# v1.net
KiCad netlist of a schematic drawn in EAGLE
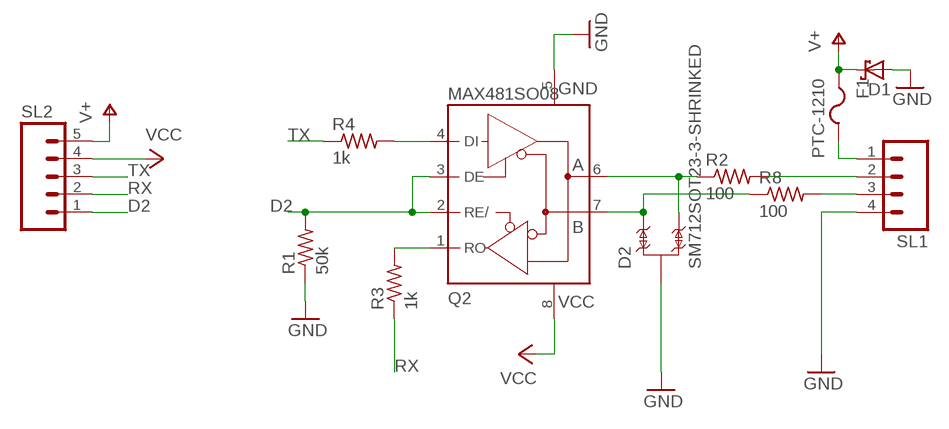
[diagram p0: schematic, sheet 1]

(export (version "E")
  (design (tool "Eeschema 10.0.6"))
  (components
    (comp (ref "D1")
      (value "SCHOTTKY-DIODESMC")
      (footprint "eagle-import:SMC")
      (libsource (lib "eagle-import") (part "SCHOTTKY-DIODESMC"))
    )
    (comp (ref "D2")
      (value "SM712SOT23-3-SHRINKED")
      (footprint "eagle-import:SOT23-3-SHRINKED")
      (libsource (lib "eagle-import") (part "SM712SOT23-3-SHRINKED"))
    )
    (comp (ref "F1")
      (value "PTC-1210")
      (footprint "eagle-import:1210")
      (libsource (lib "eagle-import") (part "PTC-1210"))
    )
    (comp (ref "Q2")
      (value "MAX481SO08")
      (footprint "eagle-import:SO08")
      (libsource (lib "eagle-import") (part "MAX481SO08"))
    )
    (comp (ref "R1")
      (value "50k")
      (footprint "eagle-import:R0603")
      (libsource (lib "eagle-import") (part "R-US_R0603"))
    )
    (comp (ref "R2")
      (value "100")
      (footprint "eagle-import:R0603")
      (libsource (lib "eagle-import") (part "R-US_R0603"))
    )
    (comp (ref "R3")
      (value "1k")
      (footprint "eagle-import:R0603")
      (libsource (lib "eagle-import") (part "R-US_R0603"))
    )
    (comp (ref "R4")
      (value "1k")
      (footprint "eagle-import:R0603")
      (libsource (lib "eagle-import") (part "R-US_R0603"))
    )
    (comp (ref "R8")
      (value "100")
      (footprint "eagle-import:R0603")
      (libsource (lib "eagle-import") (part "R-US_R0603"))
    )
    (comp (ref "SL1")
      (value "M04")
      (footprint "eagle-import:04P")
      (libsource (lib "eagle-import") (part "M04"))
    )
    (comp (ref "SL2")
      (value "M05")
      (footprint "eagle-import:05P")
      (libsource (lib "eagle-import") (part "M05"))
    )
  )
  (nets
    (net (code "1") (name "/D2") (class "Default")
      (node (ref "Q2") (pin "2") (pinfunction "RE/_2") (pintype "input"))
      (node (ref "Q2") (pin "3") (pinfunction "DE_3") (pintype "input"))
      (node (ref "R1") (pin "2") (pinfunction "2_2") (pintype "passive"))
      (node (ref "SL2") (pin "1") (pinfunction "1_1") (pintype "passive"))
    )
    (net (code "2") (name "/RX") (class "Default")
      (node (ref "R3") (pin "1") (pinfunction "1_1") (pintype "passive"))
      (node (ref "SL2") (pin "2") (pinfunction "2_2") (pintype "passive"))
    )
    (net (code "3") (name "/TX") (class "Default")
      (node (ref "R4") (pin "1") (pinfunction "1_1") (pintype "passive"))
      (node (ref "SL2") (pin "3") (pinfunction "3_3") (pintype "passive"))
    )
    (net (code "4") (name "GND") (class "Default")
      (node (ref "D1") (pin "A") (pinfunction "A_A") (pintype "passive"))
      (node (ref "D2") (pin "3") (pinfunction "3_3") (pintype "passive"))
      (node (ref "Q2") (pin "5") (pinfunction "GND_5") (pintype "power_in"))
      (node (ref "R1") (pin "1") (pinfunction "1_1") (pintype "passive"))
      (node (ref "SL1") (pin "4") (pinfunction "4_4") (pintype "passive"))
    )
    (net (code "5") (name "Net-(F1-Pad2)") (class "Default")
      (node (ref "F1") (pin "2") (pinfunction "2_2") (pintype "passive"))
      (node (ref "SL1") (pin "1") (pinfunction "1_1") (pintype "passive"))
    )
    (net (code "6") (name "Net-(Q2-A)") (class "Default")
      (node (ref "D2") (pin "1") (pinfunction "1_1") (pintype "passive"))
      (node (ref "Q2") (pin "6") (pinfunction "A_6") (pintype "passive"))
      (node (ref "R2") (pin "1") (pinfunction "1_1") (pintype "passive"))
    )
    (net (code "7") (name "Net-(Q2-B)") (class "Default")
      (node (ref "D2") (pin "2") (pinfunction "2_2") (pintype "passive"))
      (node (ref "Q2") (pin "7") (pinfunction "B_7") (pintype "passive"))
      (node (ref "R8") (pin "1") (pinfunction "1_1") (pintype "passive"))
    )
    (net (code "8") (name "Net-(Q2-DI)") (class "Default")
      (node (ref "Q2") (pin "4") (pinfunction "DI_4") (pintype "input"))
      (node (ref "R4") (pin "2") (pinfunction "2_2") (pintype "passive"))
    )
    (net (code "9") (name "Net-(Q2-RO)") (class "Default")
      (node (ref "Q2") (pin "1") (pinfunction "RO_1") (pintype "output"))
      (node (ref "R3") (pin "2") (pinfunction "2_2") (pintype "passive"))
    )
    (net (code "10") (name "Net-(R2-Pad2)") (class "Default")
      (node (ref "R2") (pin "2") (pinfunction "2_2") (pintype "passive"))
      (node (ref "SL1") (pin "2") (pinfunction "2_2") (pintype "passive"))
    )
    (net (code "11") (name "Net-(R8-Pad2)") (class "Default")
      (node (ref "R8") (pin "2") (pinfunction "2_2") (pintype "passive"))
      (node (ref "SL1") (pin "3") (pinfunction "3_3") (pintype "passive"))
    )
    (net (code "12") (name "V+") (class "Default")
      (node (ref "D1") (pin "C") (pinfunction "C_C") (pintype "passive"))
      (node (ref "F1") (pin "1") (pinfunction "1_1") (pintype "passive"))
      (node (ref "SL2") (pin "5") (pinfunction "5_5") (pintype "passive"))
    )
    (net (code "13") (name "VCC") (class "Default")
      (node (ref "Q2") (pin "8") (pinfunction "+5V_8") (pintype "power_in"))
      (node (ref "SL2") (pin "4") (pinfunction "4_4") (pintype "passive"))
    )
  )
)
